# Grove_-_Buzzer_v1_1b.net
KiCad netlist of a schematic drawn in EAGLE
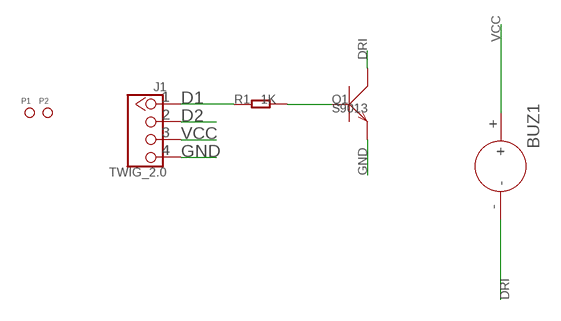
[diagram p0: schematic, sheet 1]

(export (version "E")
  (design (tool "Eeschema 10.0.6"))
  (components
    (comp (ref "BUZ1")
      (value "BUZZER-YMD12065")
      (footprint "eagle-import:2P-7.6-D12X6.5H")
      (libsource (lib "eagle-import") (part "BUZZER-YMD12065"))
    )
    (comp (ref "J1")
      (value "TWIG_2.0")
      (footprint "eagle-import:2.0_1X4")
      (libsource (lib "eagle-import") (part "TWIG_2.0"))
    )
    (comp (ref "P1")
      (value "PAD-MARK")
      (footprint "eagle-import:ROUND-MARK-1.0")
      (fields (field (name "PARTNO") "DNP"))
      (libsource (lib "eagle-import") (part "PAD-MARK"))
    )
    (comp (ref "P2")
      (value "PAD-MARK")
      (footprint "eagle-import:ROUND-MARK-1.0")
      (fields (field (name "PARTNO") "DNP"))
      (libsource (lib "eagle-import") (part "PAD-MARK"))
    )
    (comp (ref "Q1")
      (value "S9013")
      (footprint "eagle-import:SOT23")
      (libsource (lib "eagle-import") (part "TRANSISTOR-NPN-SOT23"))
    )
    (comp (ref "R1")
      (value "1K")
      (footprint "eagle-import:R0603")
      (libsource (lib "eagle-import") (part "R-0603"))
    )
  )
  (nets
    (net (code "1") (name "/D1") (class "Default")
      (node (ref "J1") (pin "1") (pinfunction "1_1") (pintype "bidirectional"))
      (node (ref "R1") (pin "1") (pinfunction "1_1") (pintype "passive"))
    )
    (net (code "2") (name "/D2") (class "Default")
      (node (ref "J1") (pin "2") (pinfunction "2_2") (pintype "bidirectional"))
    )
    (net (code "3") (name "/DRI") (class "Default")
      (node (ref "BUZ1") (pin "-") (pinfunction "-_-") (pintype "bidirectional"))
      (node (ref "Q1") (pin "3") (pinfunction "C_3") (pintype "passive"))
    )
    (net (code "4") (name "/GND") (class "Default")
      (node (ref "J1") (pin "4") (pinfunction "4_4") (pintype "bidirectional"))
      (node (ref "Q1") (pin "2") (pinfunction "E_2") (pintype "passive"))
    )
    (net (code "5") (name "/VCC") (class "Default")
      (node (ref "BUZ1") (pin "+") (pinfunction "+_+") (pintype "bidirectional"))
      (node (ref "J1") (pin "3") (pinfunction "3_3") (pintype "bidirectional"))
    )
    (net (code "6") (name "Net-(Q1-B)") (class "Default")
      (node (ref "Q1") (pin "1") (pinfunction "B_1") (pintype "passive"))
      (node (ref "R1") (pin "2") (pinfunction "2_2") (pintype "passive"))
    )
  )
)
